# 6_uart_esc_i2c.net
KiCad netlist of a schematic drawn in Altium Designer
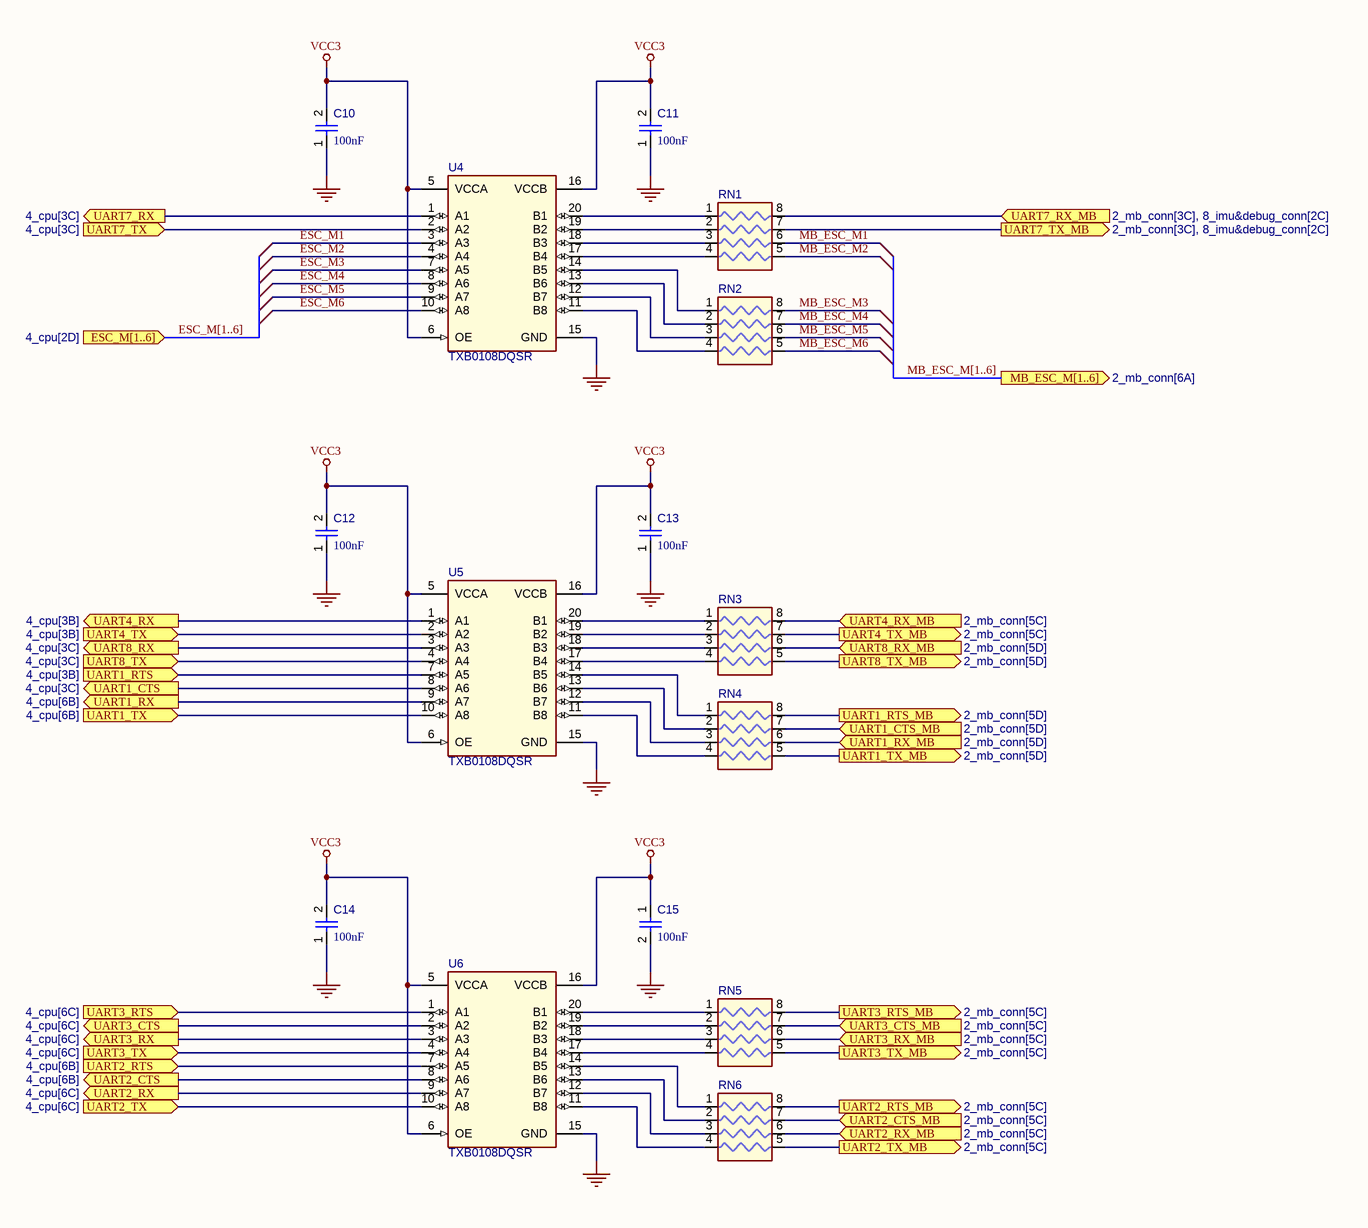
[diagram p0: 6_uart_esc_i2c.SchDoc]

(export (version "E")
  (design (tool "Eeschema 10.0.6"))
  (components
    (comp (ref "C10")
      (value "100nF")
      (footprint "CAPC0402(1005)60_L")
      (description "Chip Capacitor, 100nF +/-20%, 10V, 0402, Thickness 0.6 mm")
      (fields (field (name "TOLERANCE") "20%") (field (name "Comment") "Capacitor 100nF +/-20% 10V 0402"))
      (libsource (lib "SKA- Automa玢o de Engenharias") (part "CAP-NP-2"))
    )
    (comp (ref "C11")
      (value "100nF")
      (footprint "CAPC0402(1005)60_L")
      (description "Chip Capacitor, 100nF +/-20%, 10V, 0402, Thickness 0.6 mm")
      (fields (field (name "TOLERANCE") "20%") (field (name "Comment") "Capacitor 100nF +/-20% 10V 0402"))
      (libsource (lib "SKA- Automa玢o de Engenharias") (part "CAP-NP-2"))
    )
    (comp (ref "C12")
      (value "100nF")
      (footprint "CAPC0402(1005)60_L")
      (description "Chip Capacitor, 100nF +/-20%, 10V, 0402, Thickness 0.6 mm")
      (fields (field (name "TOLERANCE") "20%") (field (name "Comment") "Capacitor 100nF +/-20% 10V 0402"))
      (libsource (lib "SKA- Automa玢o de Engenharias") (part "CAP-NP-2"))
    )
    (comp (ref "C13")
      (value "100nF")
      (footprint "CAPC0402(1005)60_L")
      (description "Chip Capacitor, 100nF +/-20%, 10V, 0402, Thickness 0.6 mm")
      (fields (field (name "TOLERANCE") "20%") (field (name "Comment") "Capacitor 100nF +/-20% 10V 0402"))
      (libsource (lib "SKA- Automa玢o de Engenharias") (part "CAP-NP-2"))
    )
    (comp (ref "C14")
      (value "100nF")
      (footprint "CAPC0402(1005)60_L")
      (description "Chip Capacitor, 100nF +/-20%, 10V, 0402, Thickness 0.6 mm")
      (fields (field (name "TOLERANCE") "20%") (field (name "Comment") "Capacitor 100nF +/-20% 10V 0402"))
      (libsource (lib "SKA- Automa玢o de Engenharias") (part "CAP-NP-2"))
    )
    (comp (ref "C15")
      (value "100nF")
      (footprint "CAPC0402(1005)60_L")
      (description "Chip Capacitor, 100nF +/-20%, 10V, 0402, Thickness 0.6 mm")
      (fields (field (name "TOLERANCE") "20%") (field (name "Comment") "Capacitor 100nF +/-20% 10V 0402"))
      (libsource (lib "SKA- Automa玢o de Engenharias") (part "CAP-NP-2"))
    )
    (comp (ref "RN1")
      (value "Resistor 200R +/-5% 0402 62.5 mW")
      (footprint "Panasonic_EXB28")
      (fields (field (name "TOLERANCE") "5%") (field (name "POWER") "62.5mW"))
      (libsource (lib "SKA- Automa玢o de Engenharias") (part "RES-P-4"))
    )
    (comp (ref "RN2")
      (value "Resistor 200R +/-5% 0402 62.5 mW")
      (footprint "Panasonic_EXB28")
      (fields (field (name "TOLERANCE") "5%") (field (name "POWER") "62.5mW"))
      (libsource (lib "SKA- Automa玢o de Engenharias") (part "RES-P-4"))
    )
    (comp (ref "RN3")
      (value "Resistor 200R +/-5% 0402 62.5 mW")
      (footprint "Panasonic_EXB28")
      (fields (field (name "TOLERANCE") "5%") (field (name "POWER") "62.5mW"))
      (libsource (lib "SKA- Automa玢o de Engenharias") (part "RES-P-4"))
    )
    (comp (ref "RN4")
      (value "Resistor 200R +/-5% 0402 62.5 mW")
      (footprint "Panasonic_EXB28")
      (fields (field (name "TOLERANCE") "5%") (field (name "POWER") "62.5mW"))
      (libsource (lib "SKA- Automa玢o de Engenharias") (part "RES-P-4"))
    )
    (comp (ref "RN5")
      (value "Resistor 200R +/-5% 0402 62.5 mW")
      (footprint "Panasonic_EXB28")
      (fields (field (name "TOLERANCE") "5%") (field (name "POWER") "62.5mW"))
      (libsource (lib "SKA- Automa玢o de Engenharias") (part "RES-P-4"))
    )
    (comp (ref "RN6")
      (value "Resistor 200R +/-5% 0402 62.5 mW")
      (footprint "Panasonic_EXB28")
      (fields (field (name "TOLERANCE") "5%") (field (name "POWER") "62.5mW"))
      (libsource (lib "SKA- Automa玢o de Engenharias") (part "RES-P-4"))
    )
    (comp (ref "U4")
      (value "TXB0108DQSR")
      (footprint "DQS0020A_V")
      (libsource (lib "SKA- Automa玢o de Engenharias") (part "CMP-00162-7"))
    )
    (comp (ref "U5")
      (value "TXB0108DQSR")
      (footprint "DQS0020A_V")
      (libsource (lib "SKA- Automa玢o de Engenharias") (part "CMP-00162-7"))
    )
    (comp (ref "U6")
      (value "TXB0108DQSR")
      (footprint "DQS0020A_V")
      (libsource (lib "SKA- Automa玢o de Engenharias") (part "CMP-00162-7"))
    )
  )
  (nets
    (net (code "1") (name "/ESC_M1") (class "Default")
      (node (ref "U4") (pin "3") (pinfunction "A3_3") (pintype "bidirectional"))
    )
    (net (code "2") (name "/ESC_M2") (class "Default")
      (node (ref "U4") (pin "4") (pinfunction "A4_4") (pintype "bidirectional"))
    )
    (net (code "3") (name "/ESC_M3") (class "Default")
      (node (ref "U4") (pin "7") (pinfunction "A5_7") (pintype "bidirectional"))
    )
    (net (code "4") (name "/ESC_M4") (class "Default")
      (node (ref "U4") (pin "8") (pinfunction "A6_8") (pintype "bidirectional"))
    )
    (net (code "5") (name "/ESC_M5") (class "Default")
      (node (ref "U4") (pin "9") (pinfunction "A7_9") (pintype "bidirectional"))
    )
    (net (code "6") (name "/ESC_M6") (class "Default")
      (node (ref "U4") (pin "10") (pinfunction "A8_10") (pintype "bidirectional"))
    )
    (net (code "8") (name "/MB_ESC_M1") (class "Default")
      (node (ref "RN1") (pin "6") (pinfunction "2_6") (pintype "passive"))
    )
    (net (code "9") (name "/MB_ESC_M2") (class "Default")
      (node (ref "RN1") (pin "5") (pinfunction "2_5") (pintype "passive"))
    )
    (net (code "10") (name "/MB_ESC_M3") (class "Default")
      (node (ref "RN2") (pin "8") (pinfunction "2_8") (pintype "passive"))
    )
    (net (code "11") (name "/MB_ESC_M4") (class "Default")
      (node (ref "RN2") (pin "7") (pinfunction "2_7") (pintype "passive"))
    )
    (net (code "12") (name "/MB_ESC_M5") (class "Default")
      (node (ref "RN2") (pin "6") (pinfunction "2_6") (pintype "passive"))
    )
    (net (code "13") (name "/MB_ESC_M6") (class "Default")
      (node (ref "RN2") (pin "5") (pinfunction "2_5") (pintype "passive"))
    )
    (net (code "15") (name "/UART1_CTS") (class "Default")
      (node (ref "U5") (pin "8") (pinfunction "A6_8") (pintype "bidirectional"))
    )
    (net (code "16") (name "/UART1_CTS_MB") (class "Default")
      (node (ref "RN4") (pin "7") (pinfunction "2_7") (pintype "passive"))
    )
    (net (code "17") (name "/UART1_RTS") (class "Default")
      (node (ref "U5") (pin "7") (pinfunction "A5_7") (pintype "bidirectional"))
    )
    (net (code "18") (name "/UART1_RTS_MB") (class "Default")
      (node (ref "RN4") (pin "8") (pinfunction "2_8") (pintype "passive"))
    )
    (net (code "19") (name "/UART1_RX") (class "Default")
      (node (ref "U5") (pin "9") (pinfunction "A7_9") (pintype "bidirectional"))
    )
    (net (code "20") (name "/UART1_RX_MB") (class "Default")
      (node (ref "RN4") (pin "6") (pinfunction "2_6") (pintype "passive"))
    )
    (net (code "21") (name "/UART1_TX") (class "Default")
      (node (ref "U5") (pin "10") (pinfunction "A8_10") (pintype "bidirectional"))
    )
    (net (code "22") (name "/UART1_TX_MB") (class "Default")
      (node (ref "RN4") (pin "5") (pinfunction "2_5") (pintype "passive"))
    )
    (net (code "23") (name "/UART2_CTS") (class "Default")
      (node (ref "U6") (pin "8") (pinfunction "A6_8") (pintype "bidirectional"))
    )
    (net (code "24") (name "/UART2_CTS_MB") (class "Default")
      (node (ref "RN6") (pin "7") (pinfunction "2_7") (pintype "passive"))
    )
    (net (code "25") (name "/UART2_RTS") (class "Default")
      (node (ref "U6") (pin "7") (pinfunction "A5_7") (pintype "bidirectional"))
    )
    (net (code "26") (name "/UART2_RTS_MB") (class "Default")
      (node (ref "RN6") (pin "8") (pinfunction "2_8") (pintype "passive"))
    )
    (net (code "27") (name "/UART2_RX") (class "Default")
      (node (ref "U6") (pin "9") (pinfunction "A7_9") (pintype "bidirectional"))
    )
    (net (code "28") (name "/UART2_RX_MB") (class "Default")
      (node (ref "RN6") (pin "6") (pinfunction "2_6") (pintype "passive"))
    )
    (net (code "29") (name "/UART2_TX") (class "Default")
      (node (ref "U6") (pin "10") (pinfunction "A8_10") (pintype "bidirectional"))
    )
    (net (code "30") (name "/UART2_TX_MB") (class "Default")
      (node (ref "RN6") (pin "5") (pinfunction "2_5") (pintype "passive"))
    )
    (net (code "31") (name "/UART3_CTS") (class "Default")
      (node (ref "U6") (pin "2") (pinfunction "A2_2") (pintype "bidirectional"))
    )
    (net (code "32") (name "/UART3_CTS_MB") (class "Default")
      (node (ref "RN5") (pin "7") (pinfunction "2_7") (pintype "passive"))
    )
    (net (code "33") (name "/UART3_RTS") (class "Default")
      (node (ref "U6") (pin "1") (pinfunction "A1_1") (pintype "bidirectional"))
    )
    (net (code "34") (name "/UART3_RTS_MB") (class "Default")
      (node (ref "RN5") (pin "8") (pinfunction "2_8") (pintype "passive"))
    )
    (net (code "35") (name "/UART3_RX") (class "Default")
      (node (ref "U6") (pin "3") (pinfunction "A3_3") (pintype "bidirectional"))
    )
    (net (code "36") (name "/UART3_RX_MB") (class "Default")
      (node (ref "RN5") (pin "6") (pinfunction "2_6") (pintype "passive"))
    )
    (net (code "37") (name "/UART3_TX") (class "Default")
      (node (ref "U6") (pin "4") (pinfunction "A4_4") (pintype "bidirectional"))
    )
    (net (code "38") (name "/UART3_TX_MB") (class "Default")
      (node (ref "RN5") (pin "5") (pinfunction "2_5") (pintype "passive"))
    )
    (net (code "39") (name "/UART4_RX") (class "Default")
      (node (ref "U5") (pin "1") (pinfunction "A1_1") (pintype "bidirectional"))
    )
    (net (code "40") (name "/UART4_RX_MB") (class "Default")
      (node (ref "RN3") (pin "8") (pinfunction "2_8") (pintype "passive"))
    )
    (net (code "41") (name "/UART4_TX") (class "Default")
      (node (ref "U5") (pin "2") (pinfunction "A2_2") (pintype "bidirectional"))
    )
    (net (code "42") (name "/UART4_TX_MB") (class "Default")
      (node (ref "RN3") (pin "7") (pinfunction "2_7") (pintype "passive"))
    )
    (net (code "43") (name "/UART7_RX") (class "Default")
      (node (ref "U4") (pin "1") (pinfunction "A1_1") (pintype "bidirectional"))
    )
    (net (code "44") (name "/UART7_RX_MB") (class "Default")
      (node (ref "RN1") (pin "8") (pinfunction "2_8") (pintype "passive"))
    )
    (net (code "45") (name "/UART7_TX") (class "Default")
      (node (ref "U4") (pin "2") (pinfunction "A2_2") (pintype "bidirectional"))
    )
    (net (code "46") (name "/UART7_TX_MB") (class "Default")
      (node (ref "RN1") (pin "7") (pinfunction "2_7") (pintype "passive"))
    )
    (net (code "47") (name "/UART8_RX") (class "Default")
      (node (ref "U5") (pin "3") (pinfunction "A3_3") (pintype "bidirectional"))
    )
    (net (code "48") (name "/UART8_RX_MB") (class "Default")
      (node (ref "RN3") (pin "6") (pinfunction "2_6") (pintype "passive"))
    )
    (net (code "49") (name "/UART8_TX") (class "Default")
      (node (ref "U5") (pin "4") (pinfunction "A4_4") (pintype "bidirectional"))
    )
    (net (code "50") (name "/UART8_TX_MB") (class "Default")
      (node (ref "RN3") (pin "5") (pinfunction "2_5") (pintype "passive"))
    )
    (net (code "51") (name "GND") (class "Default")
      (node (ref "C10") (pin "1") (pinfunction "1_1") (pintype "passive"))
      (node (ref "C11") (pin "1") (pinfunction "1_1") (pintype "passive"))
      (node (ref "C12") (pin "1") (pinfunction "1_1") (pintype "passive"))
      (node (ref "C13") (pin "1") (pinfunction "1_1") (pintype "passive"))
      (node (ref "C14") (pin "1") (pinfunction "1_1") (pintype "passive"))
      (node (ref "C15") (pin "2") (pinfunction "2_2") (pintype "passive"))
      (node (ref "U4") (pin "15") (pinfunction "GND_15") (pintype "power_in"))
      (node (ref "U5") (pin "15") (pinfunction "GND_15") (pintype "power_in"))
      (node (ref "U6") (pin "15") (pinfunction "GND_15") (pintype "power_in"))
    )
    (net (code "52") (name "Net-(U4-B1)") (class "Default")
      (node (ref "RN1") (pin "1") (pinfunction "1_1") (pintype "passive"))
      (node (ref "U4") (pin "20") (pinfunction "B1_20") (pintype "bidirectional"))
    )
    (net (code "53") (name "Net-(U4-B2)") (class "Default")
      (node (ref "RN1") (pin "2") (pinfunction "1_2") (pintype "passive"))
      (node (ref "U4") (pin "19") (pinfunction "B2_19") (pintype "bidirectional"))
    )
    (net (code "54") (name "Net-(U4-B3)") (class "Default")
      (node (ref "RN1") (pin "3") (pinfunction "1_3") (pintype "passive"))
      (node (ref "U4") (pin "18") (pinfunction "B3_18") (pintype "bidirectional"))
    )
    (net (code "55") (name "Net-(U4-B4)") (class "Default")
      (node (ref "RN1") (pin "4") (pinfunction "1_4") (pintype "passive"))
      (node (ref "U4") (pin "17") (pinfunction "B4_17") (pintype "bidirectional"))
    )
    (net (code "56") (name "Net-(U4-B5)") (class "Default")
      (node (ref "RN2") (pin "1") (pinfunction "1_1") (pintype "passive"))
      (node (ref "U4") (pin "14") (pinfunction "B5_14") (pintype "bidirectional"))
    )
    (net (code "57") (name "Net-(U4-B6)") (class "Default")
      (node (ref "RN2") (pin "2") (pinfunction "1_2") (pintype "passive"))
      (node (ref "U4") (pin "13") (pinfunction "B6_13") (pintype "bidirectional"))
    )
    (net (code "58") (name "Net-(U4-B7)") (class "Default")
      (node (ref "RN2") (pin "3") (pinfunction "1_3") (pintype "passive"))
      (node (ref "U4") (pin "12") (pinfunction "B7_12") (pintype "bidirectional"))
    )
    (net (code "59") (name "Net-(U4-B8)") (class "Default")
      (node (ref "RN2") (pin "4") (pinfunction "1_4") (pintype "passive"))
      (node (ref "U4") (pin "11") (pinfunction "B8_11") (pintype "bidirectional"))
    )
    (net (code "60") (name "Net-(U5-B1)") (class "Default")
      (node (ref "RN3") (pin "1") (pinfunction "1_1") (pintype "passive"))
      (node (ref "U5") (pin "20") (pinfunction "B1_20") (pintype "bidirectional"))
    )
    (net (code "61") (name "Net-(U5-B2)") (class "Default")
      (node (ref "RN3") (pin "2") (pinfunction "1_2") (pintype "passive"))
      (node (ref "U5") (pin "19") (pinfunction "B2_19") (pintype "bidirectional"))
    )
    (net (code "62") (name "Net-(U5-B3)") (class "Default")
      (node (ref "RN3") (pin "3") (pinfunction "1_3") (pintype "passive"))
      (node (ref "U5") (pin "18") (pinfunction "B3_18") (pintype "bidirectional"))
    )
    (net (code "63") (name "Net-(U5-B4)") (class "Default")
      (node (ref "RN3") (pin "4") (pinfunction "1_4") (pintype "passive"))
      (node (ref "U5") (pin "17") (pinfunction "B4_17") (pintype "bidirectional"))
    )
    (net (code "64") (name "Net-(U5-B5)") (class "Default")
      (node (ref "RN4") (pin "1") (pinfunction "1_1") (pintype "passive"))
      (node (ref "U5") (pin "14") (pinfunction "B5_14") (pintype "bidirectional"))
    )
    (net (code "65") (name "Net-(U5-B6)") (class "Default")
      (node (ref "RN4") (pin "2") (pinfunction "1_2") (pintype "passive"))
      (node (ref "U5") (pin "13") (pinfunction "B6_13") (pintype "bidirectional"))
    )
    (net (code "66") (name "Net-(U5-B7)") (class "Default")
      (node (ref "RN4") (pin "3") (pinfunction "1_3") (pintype "passive"))
      (node (ref "U5") (pin "12") (pinfunction "B7_12") (pintype "bidirectional"))
    )
    (net (code "67") (name "Net-(U5-B8)") (class "Default")
      (node (ref "RN4") (pin "4") (pinfunction "1_4") (pintype "passive"))
      (node (ref "U5") (pin "11") (pinfunction "B8_11") (pintype "bidirectional"))
    )
    (net (code "68") (name "Net-(U6-B1)") (class "Default")
      (node (ref "RN5") (pin "1") (pinfunction "1_1") (pintype "passive"))
      (node (ref "U6") (pin "20") (pinfunction "B1_20") (pintype "bidirectional"))
    )
    (net (code "69") (name "Net-(U6-B2)") (class "Default")
      (node (ref "RN5") (pin "2") (pinfunction "1_2") (pintype "passive"))
      (node (ref "U6") (pin "19") (pinfunction "B2_19") (pintype "bidirectional"))
    )
    (net (code "70") (name "Net-(U6-B3)") (class "Default")
      (node (ref "RN5") (pin "3") (pinfunction "1_3") (pintype "passive"))
      (node (ref "U6") (pin "18") (pinfunction "B3_18") (pintype "bidirectional"))
    )
    (net (code "71") (name "Net-(U6-B4)") (class "Default")
      (node (ref "RN5") (pin "4") (pinfunction "1_4") (pintype "passive"))
      (node (ref "U6") (pin "17") (pinfunction "B4_17") (pintype "bidirectional"))
    )
    (net (code "72") (name "Net-(U6-B5)") (class "Default")
      (node (ref "RN6") (pin "1") (pinfunction "1_1") (pintype "passive"))
      (node (ref "U6") (pin "14") (pinfunction "B5_14") (pintype "bidirectional"))
    )
    (net (code "73") (name "Net-(U6-B6)") (class "Default")
      (node (ref "RN6") (pin "2") (pinfunction "1_2") (pintype "passive"))
      (node (ref "U6") (pin "13") (pinfunction "B6_13") (pintype "bidirectional"))
    )
    (net (code "74") (name "Net-(U6-B7)") (class "Default")
      (node (ref "RN6") (pin "3") (pinfunction "1_3") (pintype "passive"))
      (node (ref "U6") (pin "12") (pinfunction "B7_12") (pintype "bidirectional"))
    )
    (net (code "75") (name "Net-(U6-B8)") (class "Default")
      (node (ref "RN6") (pin "4") (pinfunction "1_4") (pintype "passive"))
      (node (ref "U6") (pin "11") (pinfunction "B8_11") (pintype "bidirectional"))
    )
    (net (code "76") (name "VCC3") (class "Default")
      (node (ref "C10") (pin "2") (pinfunction "2_2") (pintype "passive"))
      (node (ref "C11") (pin "2") (pinfunction "2_2") (pintype "passive"))
      (node (ref "C12") (pin "2") (pinfunction "2_2") (pintype "passive"))
      (node (ref "C13") (pin "2") (pinfunction "2_2") (pintype "passive"))
      (node (ref "C14") (pin "2") (pinfunction "2_2") (pintype "passive"))
      (node (ref "C15") (pin "1") (pinfunction "1_1") (pintype "passive"))
      (node (ref "U4") (pin "16") (pinfunction "VCCB_16") (pintype "power_in"))
      (node (ref "U4") (pin "5") (pinfunction "VCCA_5") (pintype "power_in"))
      (node (ref "U4") (pin "6") (pinfunction "OE_6") (pintype "input"))
      (node (ref "U5") (pin "16") (pinfunction "VCCB_16") (pintype "power_in"))
      (node (ref "U5") (pin "5") (pinfunction "VCCA_5") (pintype "power_in"))
      (node (ref "U5") (pin "6") (pinfunction "OE_6") (pintype "input"))
      (node (ref "U6") (pin "16") (pinfunction "VCCB_16") (pintype "power_in"))
      (node (ref "U6") (pin "5") (pinfunction "VCCA_5") (pintype "power_in"))
      (node (ref "U6") (pin "6") (pinfunction "OE_6") (pintype "input"))
    )
  )
)
